# relai-lit-electrique.net
KiCad netlist of a schematic drawn in EAGLE
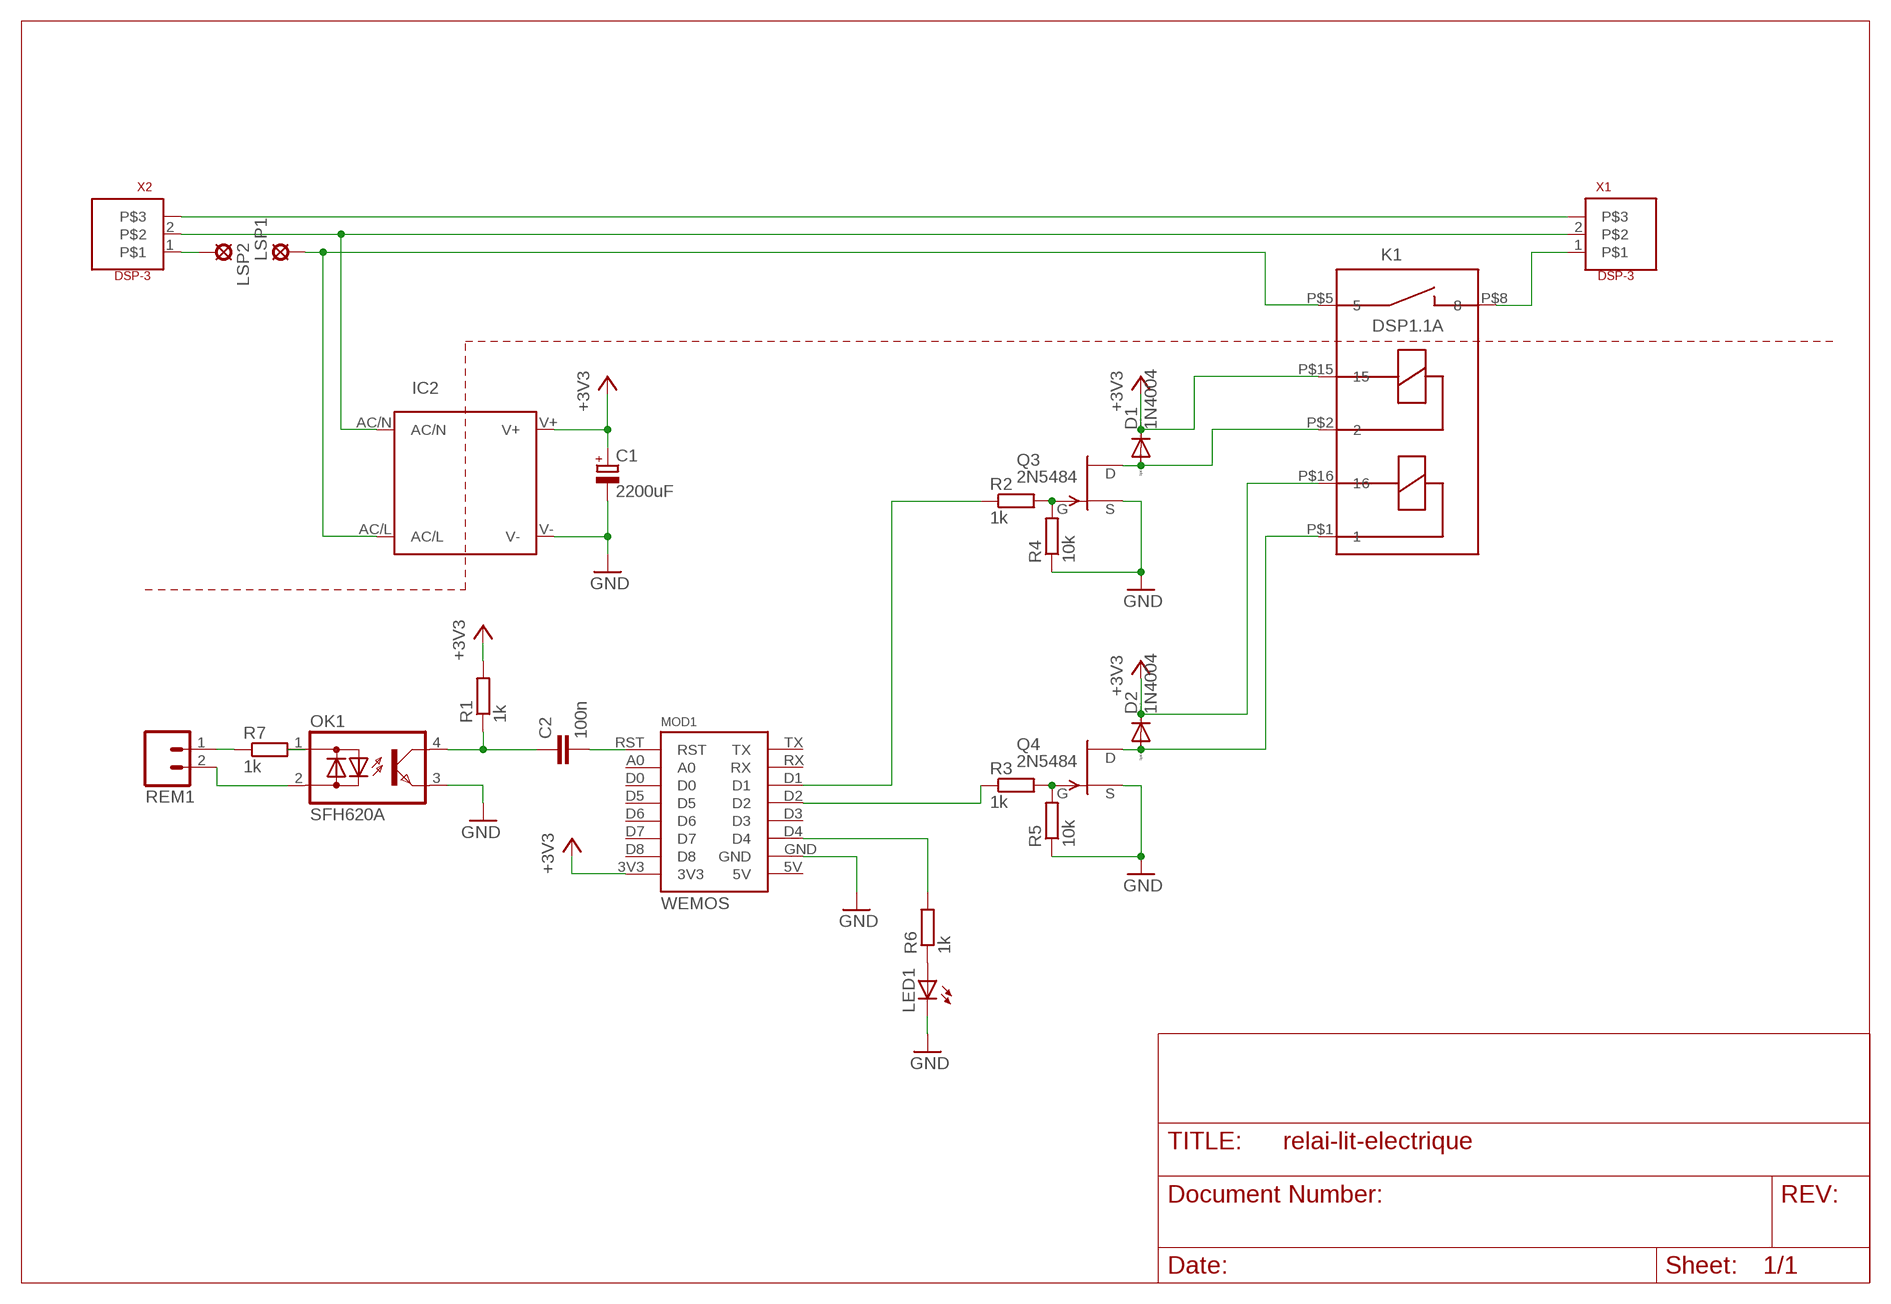
[diagram p0: schematic, sheet 1]

(export (version "E")
  (design (tool "Eeschema 10.0.6"))
  (components
    (comp (ref "C1")
      (value "2200uF")
      (footprint "eagle-import:E3,5-10")
      (libsource (lib "eagle-import") (part "CPOL-EUE3.5-10"))
    )
    (comp (ref "C2")
      (value "100n")
      (footprint "eagle-import:C025-024X044")
      (libsource (lib "eagle-import") (part "C-EU025-024X044"))
    )
    (comp (ref "D1")
      (value "1N4004")
      (footprint "eagle-import:DO41-10")
      (libsource (lib "eagle-import") (part "1N4004"))
    )
    (comp (ref "D2")
      (value "1N4004")
      (footprint "eagle-import:DO41-10")
      (libsource (lib "eagle-import") (part "1N4004"))
    )
    (comp (ref "IC2")
      (value "IRM_03")
      (footprint "eagle-import:IRM_03")
      (libsource (lib "eagle-import") (part "IRM_03"))
    )
    (comp (ref "K1")
      (value "DSP1.1A")
      (footprint "eagle-import:DSP1A")
      (libsource (lib "eagle-import") (part "DSP1.1A"))
    )
    (comp (ref "LED1")
      (value "LED3MM")
      (footprint "eagle-import:LED3MM")
      (libsource (lib "eagle-import") (part "LED3MM"))
    )
    (comp (ref "LSP1")
      (value "SE14")
      (footprint "eagle-import:SE14")
      (libsource (lib "eagle-import") (part "SE14"))
    )
    (comp (ref "LSP2")
      (value "SE14")
      (footprint "eagle-import:SE14")
      (libsource (lib "eagle-import") (part "SE14"))
    )
    (comp (ref "MOD1")
      (value "WEMOS")
      (footprint "eagle-import:WEMOS")
      (libsource (lib "eagle-import") (part "WEMOS"))
    )
    (comp (ref "OK1")
      (value "SFH620A")
      (footprint "eagle-import:DIL04")
      (fields (field (name "MPN") "SFH620A-2"))
      (libsource (lib "eagle-import") (part "SFH620A"))
    )
    (comp (ref "Q3")
      (value "2N5484")
      (footprint "eagle-import:TO92-")
      (libsource (lib "eagle-import") (part "?5482N4"))
    )
    (comp (ref "Q4")
      (value "2N5484")
      (footprint "eagle-import:TO92-")
      (libsource (lib "eagle-import") (part "?5482N4"))
    )
    (comp (ref "R1")
      (value "1k")
      (footprint "eagle-import:0204_7")
      (libsource (lib "eagle-import") (part "R-EU_0204/7"))
    )
    (comp (ref "R2")
      (value "1k")
      (footprint "eagle-import:0204_7")
      (libsource (lib "eagle-import") (part "R-EU_0204/7"))
    )
    (comp (ref "R3")
      (value "1k")
      (footprint "eagle-import:0204_7")
      (libsource (lib "eagle-import") (part "R-EU_0204/7"))
    )
    (comp (ref "R4")
      (value "10k")
      (footprint "eagle-import:0204_7")
      (libsource (lib "eagle-import") (part "R-EU_0204/7"))
    )
    (comp (ref "R5")
      (value "10k")
      (footprint "eagle-import:0204_7")
      (libsource (lib "eagle-import") (part "R-EU_0204/7"))
    )
    (comp (ref "R6")
      (value "1k")
      (footprint "eagle-import:0204_7")
      (libsource (lib "eagle-import") (part "R-EU_0204/7"))
    )
    (comp (ref "R7")
      (value "1k")
      (footprint "eagle-import:0207_10")
      (libsource (lib "eagle-import") (part "R-EU_0207/10"))
    )
    (comp (ref "REM1")
      (value "M025MM")
      (footprint "eagle-import:SCREWTERMINAL-5MM-2")
      (libsource (lib "eagle-import") (part "M025MM"))
    )
    (comp (ref "X1")
      (value "DSP-3")
      (footprint "eagle-import:RND-CONNECT-3")
      (libsource (lib "eagle-import") (part "DSP-3"))
    )
    (comp (ref "X2")
      (value "DSP-3")
      (footprint "eagle-import:RND-CONNECT-3")
      (libsource (lib "eagle-import") (part "DSP-3"))
    )
  )
  (nets
    (net (code "1") (name "+3V3") (class "Default")
      (node (ref "C1") (pin "+") (pinfunction "+_+") (pintype "passive"))
      (node (ref "D1") (pin "C") (pinfunction "C_C") (pintype "passive"))
      (node (ref "D2") (pin "C") (pinfunction "C_C") (pintype "passive"))
      (node (ref "IC2") (pin "V+") (pinfunction "V+_V+") (pintype "output"))
      (node (ref "K1") (pin "P$15") (pinfunction "15_P$15") (pintype "bidirectional"))
      (node (ref "K1") (pin "P$16") (pinfunction "16_P$16") (pintype "bidirectional"))
      (node (ref "MOD1") (pin "3V3") (pinfunction "3V3_3V3") (pintype "bidirectional"))
      (node (ref "R1") (pin "2") (pinfunction "2_2") (pintype "passive"))
    )
    (net (code "2") (name "GND") (class "Default")
      (node (ref "C1") (pin "-") (pinfunction "-_-") (pintype "passive"))
      (node (ref "IC2") (pin "V-") (pinfunction "V-_V-") (pintype "output"))
      (node (ref "LED1") (pin "K") (pinfunction "C_K") (pintype "passive"))
      (node (ref "MOD1") (pin "GND") (pinfunction "GND_GND") (pintype "bidirectional"))
      (node (ref "OK1") (pin "3") (pinfunction "E_3") (pintype "passive"))
      (node (ref "Q3") (pin "2") (pinfunction "S_2") (pintype "passive"))
      (node (ref "Q4") (pin "2") (pinfunction "S_2") (pintype "passive"))
      (node (ref "R4") (pin "1") (pinfunction "1_1") (pintype "passive"))
      (node (ref "R5") (pin "1") (pinfunction "1_1") (pintype "passive"))
    )
    (net (code "3") (name "Net-(C2-Pad2)") (class "Default")
      (node (ref "C2") (pin "2") (pinfunction "2_2") (pintype "passive"))
      (node (ref "MOD1") (pin "RST") (pinfunction "RST_RST") (pintype "bidirectional"))
    )
    (net (code "4") (name "Net-(K1-1)") (class "Default")
      (node (ref "D2") (pin "A") (pinfunction "A_A") (pintype "passive"))
      (node (ref "K1") (pin "P$1") (pinfunction "1_P$1") (pintype "bidirectional"))
      (node (ref "Q4") (pin "3") (pinfunction "D_3") (pintype "passive"))
    )
    (net (code "5") (name "Net-(K1-2)") (class "Default")
      (node (ref "D1") (pin "A") (pinfunction "A_A") (pintype "passive"))
      (node (ref "K1") (pin "P$2") (pinfunction "2_P$2") (pintype "bidirectional"))
      (node (ref "Q3") (pin "3") (pinfunction "D_3") (pintype "passive"))
    )
    (net (code "6") (name "Net-(K1-5)") (class "Default")
      (node (ref "IC2") (pin "AC/L") (pinfunction "AC/L_AC/L") (pintype "input"))
      (node (ref "K1") (pin "P$5") (pinfunction "5_P$5") (pintype "bidirectional"))
      (node (ref "LSP1") (pin "MP") (pinfunction "MP_MP") (pintype "passive"))
    )
    (net (code "7") (name "Net-(K1-8)") (class "Default")
      (node (ref "K1") (pin "P$8") (pinfunction "8_P$8") (pintype "bidirectional"))
      (node (ref "X1") (pin "1") (pinfunction "P$1_1") (pintype "bidirectional"))
    )
    (net (code "8") (name "Net-(LED1-PadA)") (class "Default")
      (node (ref "LED1") (pin "A") (pinfunction "A_A") (pintype "passive"))
      (node (ref "R6") (pin "1") (pinfunction "1_1") (pintype "passive"))
    )
    (net (code "9") (name "Net-(MOD1-PadD1)") (class "Default")
      (node (ref "MOD1") (pin "D1") (pinfunction "D1_D1") (pintype "bidirectional"))
      (node (ref "R2") (pin "1") (pinfunction "1_1") (pintype "passive"))
    )
    (net (code "10") (name "Net-(MOD1-PadD2)") (class "Default")
      (node (ref "MOD1") (pin "D2") (pinfunction "D2_D2") (pintype "bidirectional"))
      (node (ref "R3") (pin "1") (pinfunction "1_1") (pintype "passive"))
    )
    (net (code "11") (name "Net-(MOD1-PadD4)") (class "Default")
      (node (ref "MOD1") (pin "D4") (pinfunction "D4_D4") (pintype "bidirectional"))
      (node (ref "R6") (pin "2") (pinfunction "2_2") (pintype "passive"))
    )
    (net (code "12") (name "Net-(OK1-AC1)") (class "Default")
      (node (ref "OK1") (pin "1") (pinfunction "AC1_1") (pintype "passive"))
      (node (ref "R7") (pin "2") (pinfunction "2_2") (pintype "passive"))
    )
    (net (code "13") (name "Net-(OK1-AC2)") (class "Default")
      (node (ref "OK1") (pin "2") (pinfunction "AC2_2") (pintype "passive"))
      (node (ref "REM1") (pin "2") (pinfunction "2_2") (pintype "passive"))
    )
    (net (code "14") (name "Net-(OK1-C)") (class "Default")
      (node (ref "C2") (pin "1") (pinfunction "1_1") (pintype "passive"))
      (node (ref "OK1") (pin "4") (pinfunction "C_4") (pintype "passive"))
      (node (ref "R1") (pin "1") (pinfunction "1_1") (pintype "passive"))
    )
    (net (code "15") (name "Net-(Q3-G)") (class "Default")
      (node (ref "Q3") (pin "1") (pinfunction "G_1") (pintype "passive"))
      (node (ref "R2") (pin "2") (pinfunction "2_2") (pintype "passive"))
      (node (ref "R4") (pin "2") (pinfunction "2_2") (pintype "passive"))
    )
    (net (code "16") (name "Net-(Q4-G)") (class "Default")
      (node (ref "Q4") (pin "1") (pinfunction "G_1") (pintype "passive"))
      (node (ref "R3") (pin "2") (pinfunction "2_2") (pintype "passive"))
      (node (ref "R5") (pin "2") (pinfunction "2_2") (pintype "passive"))
    )
    (net (code "17") (name "Net-(R7-Pad1)") (class "Default")
      (node (ref "R7") (pin "1") (pinfunction "1_1") (pintype "passive"))
      (node (ref "REM1") (pin "1") (pinfunction "1_1") (pintype "passive"))
    )
    (net (code "18") (name "Net-(X1-P$2)") (class "Default")
      (node (ref "IC2") (pin "AC/N") (pinfunction "AC/N_AC/N") (pintype "input"))
      (node (ref "X1") (pin "2") (pinfunction "P$2_2") (pintype "bidirectional"))
      (node (ref "X2") (pin "2") (pinfunction "P$2_2") (pintype "bidirectional"))
    )
    (net (code "19") (name "Net-(X1-P$3)") (class "Default")
      (node (ref "X1") (pin "3") (pinfunction "P$3_3") (pintype "bidirectional"))
      (node (ref "X2") (pin "3") (pinfunction "P$3_3") (pintype "bidirectional"))
    )
    (net (code "20") (name "Net-(X2-P$1)") (class "Default")
      (node (ref "LSP2") (pin "MP") (pinfunction "MP_MP") (pintype "passive"))
      (node (ref "X2") (pin "1") (pinfunction "P$1_1") (pintype "bidirectional"))
    )
    (net (code "21") (name "unconnected-(MOD1-Pad5V)") (class "Default")
      (node (ref "MOD1") (pin "5V") (pinfunction "5V_5V") (pintype "bidirectional"))
    )
    (net (code "22") (name "unconnected-(MOD1-PadA0)") (class "Default")
      (node (ref "MOD1") (pin "A0") (pinfunction "A0_A0") (pintype "bidirectional"))
    )
    (net (code "23") (name "unconnected-(MOD1-PadD0)") (class "Default")
      (node (ref "MOD1") (pin "D0") (pinfunction "D0_D0") (pintype "bidirectional"))
    )
    (net (code "24") (name "unconnected-(MOD1-PadD3)") (class "Default")
      (node (ref "MOD1") (pin "D3") (pinfunction "D3_D3") (pintype "bidirectional"))
    )
    (net (code "25") (name "unconnected-(MOD1-PadD5)") (class "Default")
      (node (ref "MOD1") (pin "D5") (pinfunction "D5_D5") (pintype "bidirectional"))
    )
    (net (code "26") (name "unconnected-(MOD1-PadD6)") (class "Default")
      (node (ref "MOD1") (pin "D6") (pinfunction "D6_D6") (pintype "bidirectional"))
    )
    (net (code "27") (name "unconnected-(MOD1-PadD7)") (class "Default")
      (node (ref "MOD1") (pin "D7") (pinfunction "D7_D7") (pintype "bidirectional"))
    )
    (net (code "28") (name "unconnected-(MOD1-PadD8)") (class "Default")
      (node (ref "MOD1") (pin "D8") (pinfunction "D8_D8") (pintype "bidirectional"))
    )
    (net (code "29") (name "unconnected-(MOD1-PadRX)") (class "Default")
      (node (ref "MOD1") (pin "RX") (pinfunction "RX_RX") (pintype "bidirectional"))
    )
    (net (code "30") (name "unconnected-(MOD1-PadTX)") (class "Default")
      (node (ref "MOD1") (pin "TX") (pinfunction "TX_TX") (pintype "bidirectional"))
    )
  )
)
